# UNDER_FAST.net
KiCad netlist of a schematic drawn in EAGLE
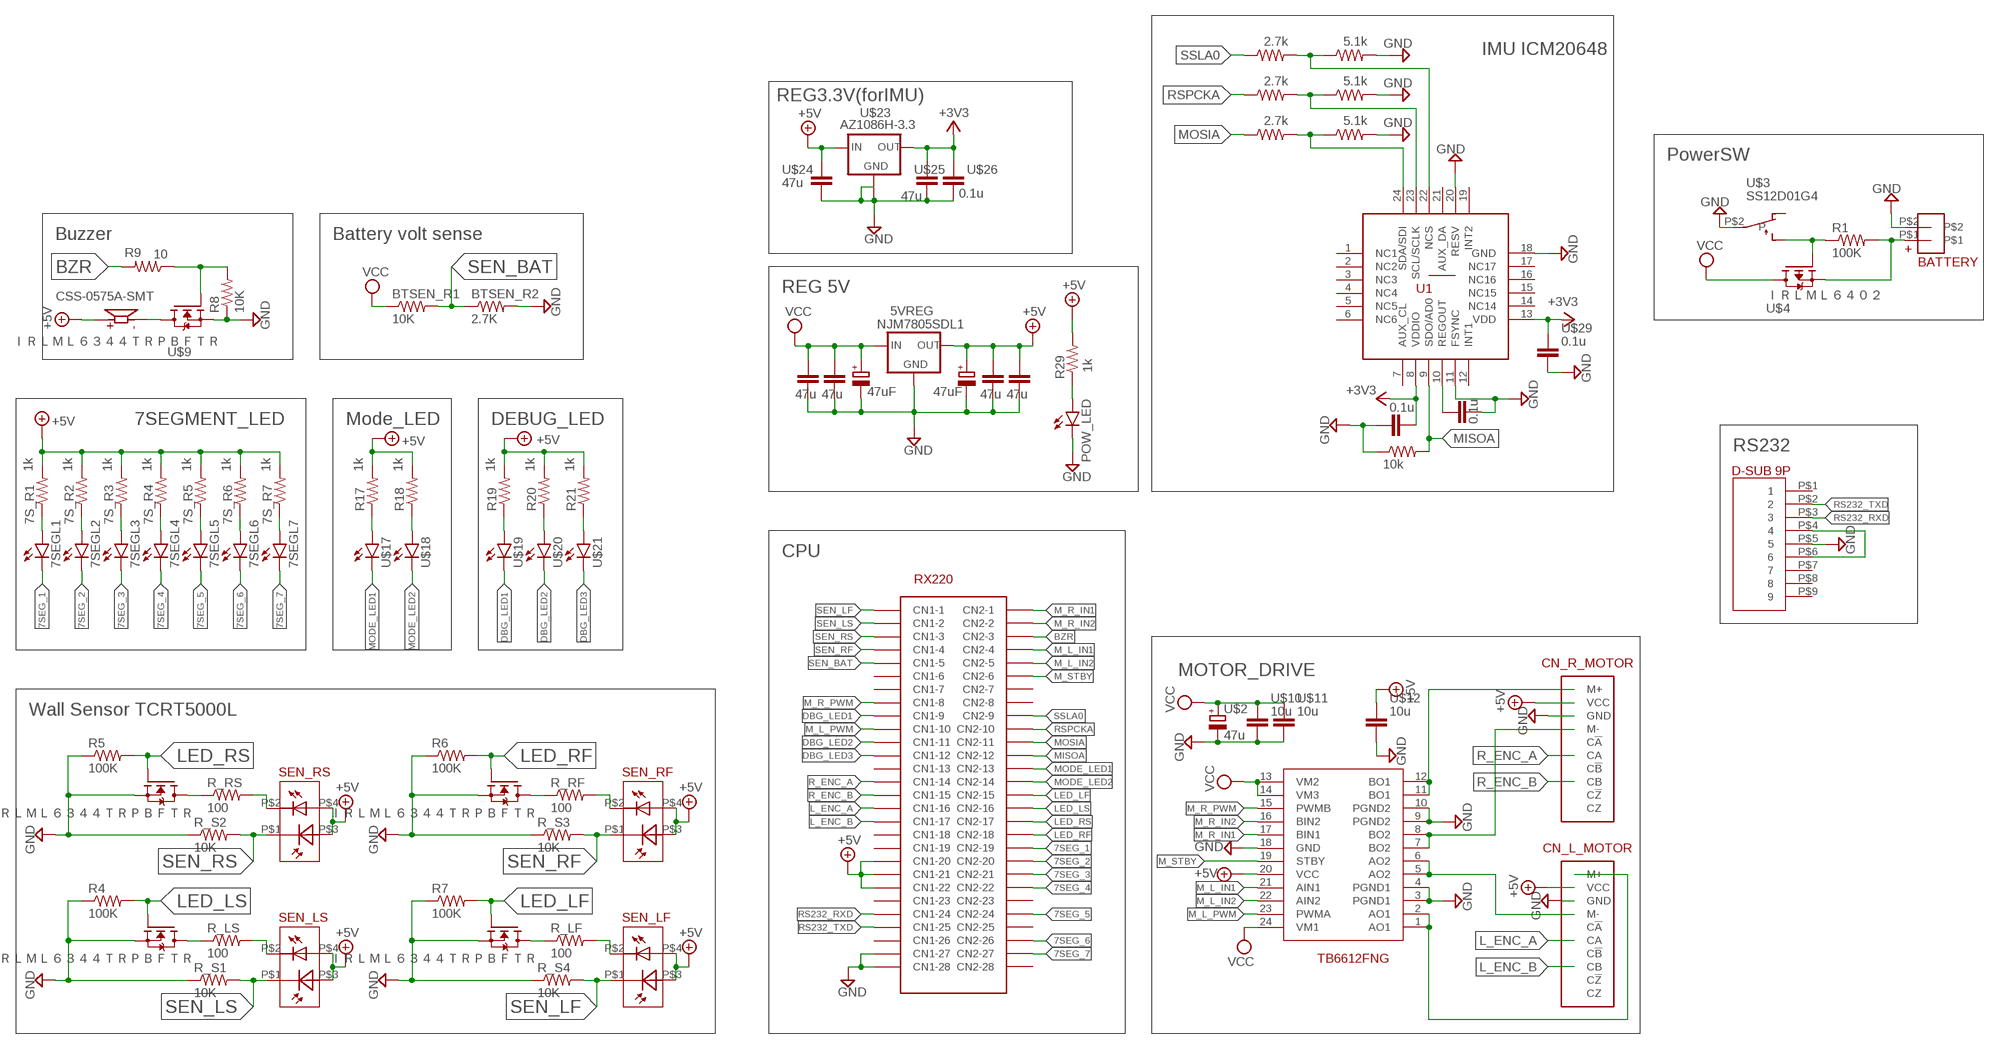
[diagram p0: schematic, sheet 1]

(export (version "E")
  (design (tool "Eeschema 10.0.6"))
  (components
    (comp (ref "5VREG")
      (value "NJM7805SDL1")
      (footprint "eagle-import:TO252")
      (libsource (lib "eagle-import") (part "NJM7805SDL1"))
    )
    (comp (ref "7SEGL1")
      (value "LED1608")
      (footprint "eagle-import:LED1608")
      (libsource (lib "eagle-import") (part "LED1608"))
    )
    (comp (ref "7SEGL2")
      (value "LED1608")
      (footprint "eagle-import:LED1608")
      (libsource (lib "eagle-import") (part "LED1608"))
    )
    (comp (ref "7SEGL3")
      (value "LED1608")
      (footprint "eagle-import:LED1608")
      (libsource (lib "eagle-import") (part "LED1608"))
    )
    (comp (ref "7SEGL4")
      (value "LED1608")
      (footprint "eagle-import:LED1608")
      (libsource (lib "eagle-import") (part "LED1608"))
    )
    (comp (ref "7SEGL5")
      (value "LED1608")
      (footprint "eagle-import:LED1608")
      (libsource (lib "eagle-import") (part "LED1608"))
    )
    (comp (ref "7SEGL6")
      (value "LED1608")
      (footprint "eagle-import:LED1608")
      (libsource (lib "eagle-import") (part "LED1608"))
    )
    (comp (ref "7SEGL7")
      (value "LED1608")
      (footprint "eagle-import:LED1608")
      (libsource (lib "eagle-import") (part "LED1608"))
    )
    (comp (ref "7S_R1")
      (value "1k")
      (footprint "eagle-import:RESC1005X40N")
      (fields
        (field (name "DIGI-KEY_PART_NUMBER") "P1.00KLCT-ND")
        (field (name "MF") "Panasonic")
        (field (name "MP") "ERJ-2RKF1001X")
      )
      (libsource (lib "eagle-import") (part "ERJ-2RKF1001X"))
    )
    (comp (ref "7S_R2")
      (value "1k")
      (footprint "eagle-import:RESC1005X40N")
      (fields
        (field (name "DIGI-KEY_PART_NUMBER") "P1.00KLCT-ND")
        (field (name "MF") "Panasonic")
        (field (name "MP") "ERJ-2RKF1001X")
      )
      (libsource (lib "eagle-import") (part "ERJ-2RKF1001X"))
    )
    (comp (ref "7S_R3")
      (value "1k")
      (footprint "eagle-import:RESC1005X40N")
      (fields
        (field (name "DIGI-KEY_PART_NUMBER") "P1.00KLCT-ND")
        (field (name "MF") "Panasonic")
        (field (name "MP") "ERJ-2RKF1001X")
      )
      (libsource (lib "eagle-import") (part "ERJ-2RKF1001X"))
    )
    (comp (ref "7S_R4")
      (value "1k")
      (footprint "eagle-import:RESC1005X40N")
      (fields
        (field (name "DIGI-KEY_PART_NUMBER") "P1.00KLCT-ND")
        (field (name "MF") "Panasonic")
        (field (name "MP") "ERJ-2RKF1001X")
      )
      (libsource (lib "eagle-import") (part "ERJ-2RKF1001X"))
    )
    (comp (ref "7S_R5")
      (value "1k")
      (footprint "eagle-import:RESC1005X40N")
      (fields
        (field (name "DIGI-KEY_PART_NUMBER") "P1.00KLCT-ND")
        (field (name "MF") "Panasonic")
        (field (name "MP") "ERJ-2RKF1001X")
      )
      (libsource (lib "eagle-import") (part "ERJ-2RKF1001X"))
    )
    (comp (ref "7S_R6")
      (value "1k")
      (footprint "eagle-import:RESC1005X40N")
      (fields
        (field (name "DIGI-KEY_PART_NUMBER") "P1.00KLCT-ND")
        (field (name "MF") "Panasonic")
        (field (name "MP") "ERJ-2RKF1001X")
      )
      (libsource (lib "eagle-import") (part "ERJ-2RKF1001X"))
    )
    (comp (ref "7S_R7")
      (value "1k")
      (footprint "eagle-import:RESC1005X40N")
      (fields
        (field (name "DIGI-KEY_PART_NUMBER") "P1.00KLCT-ND")
        (field (name "MF") "Panasonic")
        (field (name "MP") "ERJ-2RKF1001X")
      )
      (libsource (lib "eagle-import") (part "ERJ-2RKF1001X"))
    )
    (comp (ref "BATTERY")
      (value "DF3A_2P_2DSA_CONNECTOR")
      (footprint "eagle-import:DF3A_2P_2DSA_CONNECTOR")
      (libsource (lib "eagle-import") (part "DF3A_2P_2DSA_CONNECTOR"))
    )
    (comp (ref "BTSEN_R1")
      (value "10K")
      (footprint "eagle-import:RESC1005X40N")
      (fields
        (field (name "DIGI-KEY_PART_NUMBER") "P1.00KLCT-ND")
        (field (name "MF") "Panasonic")
        (field (name "MP") "ERJ-2RKF1001X")
      )
      (libsource (lib "eagle-import") (part "ERJ-2RKF1001X"))
    )
    (comp (ref "BTSEN_R2")
      (value "2.7K")
      (footprint "eagle-import:RESC1005X40N")
      (fields
        (field (name "DIGI-KEY_PART_NUMBER") "P1.00KLCT-ND")
        (field (name "MF") "Panasonic")
        (field (name "MP") "ERJ-2RKF1001X")
      )
      (libsource (lib "eagle-import") (part "ERJ-2RKF1001X"))
    )
    (comp (ref "C1")
      (value "47u")
      (footprint "eagle-import:CAPC3225X270N")
      (libsource (lib "eagle-import") (part "C3225"))
    )
    (comp (ref "C2")
      (value "47u")
      (footprint "eagle-import:CAPC3225X270N")
      (libsource (lib "eagle-import") (part "C3225"))
    )
    (comp (ref "C3")
      (value "47u")
      (footprint "eagle-import:CAPC3225X270N")
      (libsource (lib "eagle-import") (part "C3225"))
    )
    (comp (ref "C4")
      (value "47u")
      (footprint "eagle-import:CAPC3225X270N")
      (libsource (lib "eagle-import") (part "C3225"))
    )
    (comp (ref "CLK_R1")
      (value "2.7k")
      (footprint "eagle-import:RESC1005X40N")
      (fields
        (field (name "DIGI-KEY_PART_NUMBER") "P1.00KLCT-ND")
        (field (name "MF") "Panasonic")
        (field (name "MP") "ERJ-2RKF1001X")
      )
      (libsource (lib "eagle-import") (part "ERJ-2RKF1001X"))
    )
    (comp (ref "CLK_R2")
      (value "5.1k")
      (footprint "eagle-import:RESC1005X40N")
      (fields
        (field (name "DIGI-KEY_PART_NUMBER") "P1.00KLCT-ND")
        (field (name "MF") "Panasonic")
        (field (name "MP") "ERJ-2RKF1001X")
      )
      (libsource (lib "eagle-import") (part "ERJ-2RKF1001X"))
    )
    (comp (ref "CN_L_MOTOR")
      (value "CN_MOTOR")
      (footprint "eagle-import:CN_MOTOR")
      (libsource (lib "eagle-import") (part "CN_MOTOR"))
    )
    (comp (ref "CN_R_MOTOR")
      (value "CN_MOTOR")
      (footprint "eagle-import:CN_MOTOR")
      (libsource (lib "eagle-import") (part "CN_MOTOR"))
    )
    (comp (ref "EC1")
      (value "47uF")
      (footprint "eagle-import:CAPAE660X800N")
      (libsource (lib "eagle-import") (part "EEE-HC1E470XP"))
    )
    (comp (ref "EC2")
      (value "47uF")
      (footprint "eagle-import:CAPAE660X800N")
      (libsource (lib "eagle-import") (part "EEE-HC1E470XP"))
    )
    (comp (ref "LS1")
      (value "CSS-0575A-SMT")
      (footprint "eagle-import:CUI_CSS-0575A-SMT")
      (fields
        (field (name "DIGI-KEY_PART_NUMBER") "102-2201-1-ND")
        (field (name "MF") "CUI Devices")
        (field (name "MP") "CSS-0575A-SMT-TR")
      )
      (libsource (lib "eagle-import") (part "CSS-0575A-SMT"))
    )
    (comp (ref "MISO_R")
      (value "10k")
      (footprint "eagle-import:RESC1005X40N")
      (fields
        (field (name "DIGI-KEY_PART_NUMBER") "P1.00KLCT-ND")
        (field (name "MF") "Panasonic")
        (field (name "MP") "ERJ-2RKF1001X")
      )
      (libsource (lib "eagle-import") (part "ERJ-2RKF1001X"))
    )
    (comp (ref "MOSI_R1")
      (value "2.7k")
      (footprint "eagle-import:RESC1005X40N")
      (fields
        (field (name "DIGI-KEY_PART_NUMBER") "P1.00KLCT-ND")
        (field (name "MF") "Panasonic")
        (field (name "MP") "ERJ-2RKF1001X")
      )
      (libsource (lib "eagle-import") (part "ERJ-2RKF1001X"))
    )
    (comp (ref "MOSI_R2")
      (value "5.1k")
      (footprint "eagle-import:RESC1005X40N")
      (fields
        (field (name "DIGI-KEY_PART_NUMBER") "P1.00KLCT-ND")
        (field (name "MF") "Panasonic")
        (field (name "MP") "ERJ-2RKF1001X")
      )
      (libsource (lib "eagle-import") (part "ERJ-2RKF1001X"))
    )
    (comp (ref "NCS_R1")
      (value "2.7k")
      (footprint "eagle-import:RESC1005X40N")
      (fields
        (field (name "DIGI-KEY_PART_NUMBER") "P1.00KLCT-ND")
        (field (name "MF") "Panasonic")
        (field (name "MP") "ERJ-2RKF1001X")
      )
      (libsource (lib "eagle-import") (part "ERJ-2RKF1001X"))
    )
    (comp (ref "NCS_R2")
      (value "5.1k")
      (footprint "eagle-import:RESC1005X40N")
      (fields
        (field (name "DIGI-KEY_PART_NUMBER") "P1.00KLCT-ND")
        (field (name "MF") "Panasonic")
        (field (name "MP") "ERJ-2RKF1001X")
      )
      (libsource (lib "eagle-import") (part "ERJ-2RKF1001X"))
    )
    (comp (ref "POW_LED")
      (value "LED1608")
      (footprint "eagle-import:LED1608")
      (libsource (lib "eagle-import") (part "LED1608"))
    )
    (comp (ref "R1")
      (value "100K")
      (footprint "eagle-import:RESC1005X40N")
      (fields
        (field (name "DIGI-KEY_PART_NUMBER") "P1.00KLCT-ND")
        (field (name "MF") "Panasonic")
        (field (name "MP") "ERJ-2RKF1001X")
      )
      (libsource (lib "eagle-import") (part "ERJ-2RKF1001X"))
    )
    (comp (ref "R4")
      (value "100K")
      (footprint "eagle-import:RESC1005X40N")
      (fields
        (field (name "DIGI-KEY_PART_NUMBER") "P1.00KLCT-ND")
        (field (name "MF") "Panasonic")
        (field (name "MP") "ERJ-2RKF1001X")
      )
      (libsource (lib "eagle-import") (part "ERJ-2RKF1001X"))
    )
    (comp (ref "R5")
      (value "100K")
      (footprint "eagle-import:RESC1005X40N")
      (fields
        (field (name "DIGI-KEY_PART_NUMBER") "P1.00KLCT-ND")
        (field (name "MF") "Panasonic")
        (field (name "MP") "ERJ-2RKF1001X")
      )
      (libsource (lib "eagle-import") (part "ERJ-2RKF1001X"))
    )
    (comp (ref "R6")
      (value "100K")
      (footprint "eagle-import:RESC1005X40N")
      (fields
        (field (name "DIGI-KEY_PART_NUMBER") "P1.00KLCT-ND")
        (field (name "MF") "Panasonic")
        (field (name "MP") "ERJ-2RKF1001X")
      )
      (libsource (lib "eagle-import") (part "ERJ-2RKF1001X"))
    )
    (comp (ref "R7")
      (value "100K")
      (footprint "eagle-import:RESC1005X40N")
      (fields
        (field (name "DIGI-KEY_PART_NUMBER") "P1.00KLCT-ND")
        (field (name "MF") "Panasonic")
        (field (name "MP") "ERJ-2RKF1001X")
      )
      (libsource (lib "eagle-import") (part "ERJ-2RKF1001X"))
    )
    (comp (ref "R8")
      (value "10K")
      (footprint "eagle-import:RESC1005X40N")
      (fields
        (field (name "DIGI-KEY_PART_NUMBER") "P1.00KLCT-ND")
        (field (name "MF") "Panasonic")
        (field (name "MP") "ERJ-2RKF1001X")
      )
      (libsource (lib "eagle-import") (part "ERJ-2RKF1001X"))
    )
    (comp (ref "R9")
      (value "10")
      (footprint "eagle-import:RESC1005X40N")
      (fields
        (field (name "DIGI-KEY_PART_NUMBER") "P1.00KLCT-ND")
        (field (name "MF") "Panasonic")
        (field (name "MP") "ERJ-2RKF1001X")
      )
      (libsource (lib "eagle-import") (part "ERJ-2RKF1001X"))
    )
    (comp (ref "R17")
      (value "1k")
      (footprint "eagle-import:RESC1005X40N")
      (fields
        (field (name "DIGI-KEY_PART_NUMBER") "P1.00KLCT-ND")
        (field (name "MF") "Panasonic")
        (field (name "MP") "ERJ-2RKF1001X")
      )
      (libsource (lib "eagle-import") (part "ERJ-2RKF1001X"))
    )
    (comp (ref "R18")
      (value "1k")
      (footprint "eagle-import:RESC1005X40N")
      (fields
        (field (name "DIGI-KEY_PART_NUMBER") "P1.00KLCT-ND")
        (field (name "MF") "Panasonic")
        (field (name "MP") "ERJ-2RKF1001X")
      )
      (libsource (lib "eagle-import") (part "ERJ-2RKF1001X"))
    )
    (comp (ref "R19")
      (value "1k")
      (footprint "eagle-import:RESC1005X40N")
      (fields
        (field (name "DIGI-KEY_PART_NUMBER") "P1.00KLCT-ND")
        (field (name "MF") "Panasonic")
        (field (name "MP") "ERJ-2RKF1001X")
      )
      (libsource (lib "eagle-import") (part "ERJ-2RKF1001X"))
    )
    (comp (ref "R20")
      (value "1k")
      (footprint "eagle-import:RESC1005X40N")
      (fields
        (field (name "DIGI-KEY_PART_NUMBER") "P1.00KLCT-ND")
        (field (name "MF") "Panasonic")
        (field (name "MP") "ERJ-2RKF1001X")
      )
      (libsource (lib "eagle-import") (part "ERJ-2RKF1001X"))
    )
    (comp (ref "R21")
      (value "1k")
      (footprint "eagle-import:RESC1005X40N")
      (fields
        (field (name "DIGI-KEY_PART_NUMBER") "P1.00KLCT-ND")
        (field (name "MF") "Panasonic")
        (field (name "MP") "ERJ-2RKF1001X")
      )
      (libsource (lib "eagle-import") (part "ERJ-2RKF1001X"))
    )
    (comp (ref "R29")
      (value "1k")
      (footprint "eagle-import:RESC1005X40N")
      (fields
        (field (name "DIGI-KEY_PART_NUMBER") "P1.00KLCT-ND")
        (field (name "MF") "Panasonic")
        (field (name "MP") "ERJ-2RKF1001X")
      )
      (libsource (lib "eagle-import") (part "ERJ-2RKF1001X"))
    )
    (comp (ref "R_LF")
      (value "100")
      (footprint "eagle-import:RESC1005X40N")
      (fields
        (field (name "DIGI-KEY_PART_NUMBER") "P1.00KLCT-ND")
        (field (name "MF") "Panasonic")
        (field (name "MP") "ERJ-2RKF1001X")
      )
      (libsource (lib "eagle-import") (part "ERJ-2RKF1001X"))
    )
    (comp (ref "R_LS")
      (value "100")
      (footprint "eagle-import:RESC1005X40N")
      (fields
        (field (name "DIGI-KEY_PART_NUMBER") "P1.00KLCT-ND")
        (field (name "MF") "Panasonic")
        (field (name "MP") "ERJ-2RKF1001X")
      )
      (libsource (lib "eagle-import") (part "ERJ-2RKF1001X"))
    )
    (comp (ref "R_RF")
      (value "100")
      (footprint "eagle-import:RESC1005X40N")
      (fields
        (field (name "DIGI-KEY_PART_NUMBER") "P1.00KLCT-ND")
        (field (name "MF") "Panasonic")
        (field (name "MP") "ERJ-2RKF1001X")
      )
      (libsource (lib "eagle-import") (part "ERJ-2RKF1001X"))
    )
    (comp (ref "R_RS")
      (value "100")
      (footprint "eagle-import:RESC1005X40N")
      (fields
        (field (name "DIGI-KEY_PART_NUMBER") "P1.00KLCT-ND")
        (field (name "MF") "Panasonic")
        (field (name "MP") "ERJ-2RKF1001X")
      )
      (libsource (lib "eagle-import") (part "ERJ-2RKF1001X"))
    )
    (comp (ref "R_S1")
      (value "10K")
      (footprint "eagle-import:RESC1005X40N")
      (fields
        (field (name "DIGI-KEY_PART_NUMBER") "P1.00KLCT-ND")
        (field (name "MF") "Panasonic")
        (field (name "MP") "ERJ-2RKF1001X")
      )
      (libsource (lib "eagle-import") (part "ERJ-2RKF1001X"))
    )
    (comp (ref "R_S2")
      (value "10K")
      (footprint "eagle-import:RESC1005X40N")
      (fields
        (field (name "DIGI-KEY_PART_NUMBER") "P1.00KLCT-ND")
        (field (name "MF") "Panasonic")
        (field (name "MP") "ERJ-2RKF1001X")
      )
      (libsource (lib "eagle-import") (part "ERJ-2RKF1001X"))
    )
    (comp (ref "R_S3")
      (value "10K")
      (footprint "eagle-import:RESC1005X40N")
      (fields
        (field (name "DIGI-KEY_PART_NUMBER") "P1.00KLCT-ND")
        (field (name "MF") "Panasonic")
        (field (name "MP") "ERJ-2RKF1001X")
      )
      (libsource (lib "eagle-import") (part "ERJ-2RKF1001X"))
    )
    (comp (ref "R_S4")
      (value "10K")
      (footprint "eagle-import:RESC1005X40N")
      (fields
        (field (name "DIGI-KEY_PART_NUMBER") "P1.00KLCT-ND")
        (field (name "MF") "Panasonic")
        (field (name "MP") "ERJ-2RKF1001X")
      )
      (libsource (lib "eagle-import") (part "ERJ-2RKF1001X"))
    )
    (comp (ref "SEN_LF")
      (value "TCRT5000L")
      (footprint "eagle-import:TCRT5000L_PHOTO")
      (libsource (lib "eagle-import") (part "TCRT5000L"))
    )
    (comp (ref "SEN_LS")
      (value "TCRT5000L")
      (footprint "eagle-import:TCRT5000L_PHOTO")
      (libsource (lib "eagle-import") (part "TCRT5000L"))
    )
    (comp (ref "SEN_RF")
      (value "TCRT5000L")
      (footprint "eagle-import:TCRT5000L_PHOTO")
      (libsource (lib "eagle-import") (part "TCRT5000L"))
    )
    (comp (ref "SEN_RS")
      (value "TCRT5000L")
      (footprint "eagle-import:TCRT5000L_PHOTO")
      (libsource (lib "eagle-import") (part "TCRT5000L"))
    )
    (comp (ref "TB6612FNG")
      (value "TB6612FNG")
      (footprint "eagle-import:SOP65P760X160-24N")
      (libsource (lib "eagle-import") (part "TB6612FNG"))
    )
    (comp (ref "U$1")
      (value "RX220_BOARD")
      (footprint "eagle-import:RX220_BOARD")
      (libsource (lib "eagle-import") (part "RX220_BOARD"))
    )
    (comp (ref "U$2")
      (value "47u")
      (footprint "eagle-import:CAPAE660X800N")
      (libsource (lib "eagle-import") (part "EEE-HC1E470XP"))
    )
    (comp (ref "U$3")
      (value "SS12D01G4")
      (footprint "eagle-import:SS12D01G4")
      (libsource (lib "eagle-import") (part "SS12D01G4"))
    )
    (comp (ref "U$4")
      (value "ＩＲＬＭＬ６４０２")
      (footprint "eagle-import:SOT23")
      (libsource (lib "eagle-import") (part "ＩＲＬＭＬ６４０２"))
    )
    (comp (ref "U$5")
      (value "ＩＲＬＭＬ６３４４ＴＲＰＢＦＴＲ")
      (footprint "eagle-import:SOT23")
      (libsource (lib "eagle-import") (part "ＩＲＬＭＬ６３４４ＴＲＰＢＦＴＲ"))
    )
    (comp (ref "U$6")
      (value "ＩＲＬＭＬ６３４４ＴＲＰＢＦＴＲ")
      (footprint "eagle-import:SOT23")
      (libsource (lib "eagle-import") (part "ＩＲＬＭＬ６３４４ＴＲＰＢＦＴＲ"))
    )
    (comp (ref "U$7")
      (value "ＩＲＬＭＬ６３４４ＴＲＰＢＦＴＲ")
      (footprint "eagle-import:SOT23")
      (libsource (lib "eagle-import") (part "ＩＲＬＭＬ６３４４ＴＲＰＢＦＴＲ"))
    )
    (comp (ref "U$8")
      (value "ＩＲＬＭＬ６３４４ＴＲＰＢＦＴＲ")
      (footprint "eagle-import:SOT23")
      (libsource (lib "eagle-import") (part "ＩＲＬＭＬ６３４４ＴＲＰＢＦＴＲ"))
    )
    (comp (ref "U$9")
      (value "ＩＲＬＭＬ６３４４ＴＲＰＢＦＴＲ")
      (footprint "eagle-import:SOT23")
      (libsource (lib "eagle-import") (part "ＩＲＬＭＬ６３４４ＴＲＰＢＦＴＲ"))
    )
    (comp (ref "U$10")
      (value "10u")
      (footprint "eagle-import:CAPC3216X180N")
      (libsource (lib "eagle-import") (part "CL31A106KBHNNNE"))
    )
    (comp (ref "U$11")
      (value "10u")
      (footprint "eagle-import:CAPC3216X180N")
      (libsource (lib "eagle-import") (part "CL31A106KBHNNNE"))
    )
    (comp (ref "U$12")
      (value "10u")
      (footprint "eagle-import:CAPC3216X180N")
      (libsource (lib "eagle-import") (part "CL31A106KBHNNNE"))
    )
    (comp (ref "U$13")
      (value "D-SUB")
      (footprint "eagle-import:D-SUB")
      (libsource (lib "eagle-import") (part "D-SUB"))
    )
    (comp (ref "U$17")
      (value "LED1608")
      (footprint "eagle-import:LED1608")
      (libsource (lib "eagle-import") (part "LED1608"))
    )
    (comp (ref "U$18")
      (value "LED1608")
      (footprint "eagle-import:LED1608")
      (libsource (lib "eagle-import") (part "LED1608"))
    )
    (comp (ref "U$19")
      (value "LED1608")
      (footprint "eagle-import:LED1608")
      (libsource (lib "eagle-import") (part "LED1608"))
    )
    (comp (ref "U$20")
      (value "LED1608")
      (footprint "eagle-import:LED1608")
      (libsource (lib "eagle-import") (part "LED1608"))
    )
    (comp (ref "U$21")
      (value "LED1608")
      (footprint "eagle-import:LED1608")
      (libsource (lib "eagle-import") (part "LED1608"))
    )
    (comp (ref "U$23")
      (value "AZ1086H-3.3")
      (footprint "eagle-import:SOT223")
      (libsource (lib "eagle-import") (part "AZ1086H-3.3"))
    )
    (comp (ref "U$24")
      (value "47u")
      (footprint "eagle-import:CAPC3225X270N")
      (libsource (lib "eagle-import") (part "C3225"))
    )
    (comp (ref "U$25")
      (value "47u")
      (footprint "eagle-import:CAPC3225X270N")
      (libsource (lib "eagle-import") (part "C3225"))
    )
    (comp (ref "U$26")
      (value "0.1u")
      (footprint "eagle-import:CAPC1005X55N")
      (libsource (lib "eagle-import") (part "C1005"))
    )
    (comp (ref "U$27")
      (value "0.1u")
      (footprint "eagle-import:CAPC1005X55N")
      (libsource (lib "eagle-import") (part "C1005"))
    )
    (comp (ref "U$28")
      (value "0.1u")
      (footprint "eagle-import:CAPC1005X55N")
      (libsource (lib "eagle-import") (part "C1005"))
    )
    (comp (ref "U$29")
      (value "0.1u")
      (footprint "eagle-import:CAPC1005X55N")
      (libsource (lib "eagle-import") (part "C1005"))
    )
    (comp (ref "U1")
      (value "ICM-20648")
      (footprint "eagle-import:QFN40P300X300X95-24N")
      (fields (field (name "DIGI-KEY_PART_NUMBER") "1428-1061-1-ND") (field (name "MF") "TDK InvenSense"))
      (libsource (lib "eagle-import") (part "ICM-20648"))
    )
  )
  (nets
    (net (code "1") (name "+3V3") (class "Default")
      (node (ref "U$23") (pin "2") (pinfunction "OUT_2") (pintype "passive"))
      (node (ref "U$25") (pin "1") (pinfunction "1_1") (pintype "passive"))
      (node (ref "U$26") (pin "1") (pinfunction "1_1") (pintype "passive"))
      (node (ref "U$28") (pin "1") (pinfunction "1_1") (pintype "passive"))
      (node (ref "U$29") (pin "1") (pinfunction "1_1") (pintype "passive"))
      (node (ref "U1") (pin "13") (pinfunction "VDD_13") (pintype "bidirectional"))
      (node (ref "U1") (pin "8") (pinfunction "VDDIO_8") (pintype "bidirectional"))
    )
    (net (code "2") (name "+5V") (class "Default")
      (node (ref "5VREG") (pin "2") (pinfunction "OUT_2") (pintype "passive"))
      (node (ref "7S_R1") (pin "2") (pinfunction "2_2") (pintype "passive"))
      (node (ref "7S_R2") (pin "2") (pinfunction "2_2") (pintype "passive"))
      (node (ref "7S_R3") (pin "2") (pinfunction "2_2") (pintype "passive"))
      (node (ref "7S_R4") (pin "2") (pinfunction "2_2") (pintype "passive"))
      (node (ref "7S_R5") (pin "2") (pinfunction "2_2") (pintype "passive"))
      (node (ref "7S_R6") (pin "2") (pinfunction "2_2") (pintype "passive"))
      (node (ref "7S_R7") (pin "2") (pinfunction "2_2") (pintype "passive"))
      (node (ref "C3") (pin "1") (pinfunction "1_1") (pintype "passive"))
      (node (ref "C4") (pin "1") (pinfunction "1_1") (pintype "passive"))
      (node (ref "CN_L_MOTOR") (pin "P$2") (pinfunction "VCC_P$2") (pintype "bidirectional"))
      (node (ref "CN_R_MOTOR") (pin "P$2") (pinfunction "VCC_P$2") (pintype "bidirectional"))
      (node (ref "EC2") (pin "1") (pinfunction "+_1") (pintype "passive"))
      (node (ref "LS1") (pin "1") (pinfunction "P_1") (pintype "passive"))
      (node (ref "R17") (pin "2") (pinfunction "2_2") (pintype "passive"))
      (node (ref "R18") (pin "2") (pinfunction "2_2") (pintype "passive"))
      (node (ref "R19") (pin "2") (pinfunction "2_2") (pintype "passive"))
      (node (ref "R20") (pin "2") (pinfunction "2_2") (pintype "passive"))
      (node (ref "R21") (pin "2") (pinfunction "2_2") (pintype "passive"))
      (node (ref "R29") (pin "2") (pinfunction "2_2") (pintype "passive"))
      (node (ref "SEN_LF") (pin "P$3") (pinfunction "DIODE+_P$3") (pintype "bidirectional"))
      (node (ref "SEN_LF") (pin "P$4") (pinfunction "LED+_P$4") (pintype "bidirectional"))
      (node (ref "SEN_LS") (pin "P$3") (pinfunction "DIODE+_P$3") (pintype "bidirectional"))
      (node (ref "SEN_LS") (pin "P$4") (pinfunction "LED+_P$4") (pintype "bidirectional"))
      (node (ref "SEN_RF") (pin "P$3") (pinfunction "DIODE+_P$3") (pintype "bidirectional"))
      (node (ref "SEN_RF") (pin "P$4") (pinfunction "LED+_P$4") (pintype "bidirectional"))
      (node (ref "SEN_RS") (pin "P$3") (pinfunction "DIODE+_P$3") (pintype "bidirectional"))
      (node (ref "SEN_RS") (pin "P$4") (pinfunction "LED+_P$4") (pintype "bidirectional"))
      (node (ref "TB6612FNG") (pin "20") (pinfunction "VCC_20") (pintype "bidirectional"))
      (node (ref "U$1") (pin "P$20") (pinfunction "CN1-20_P$20") (pintype "bidirectional"))
      (node (ref "U$1") (pin "P$21") (pinfunction "CN1-21_P$21") (pintype "bidirectional"))
      (node (ref "U$1") (pin "P$22") (pinfunction "CN1-22_P$22") (pintype "bidirectional"))
      (node (ref "U$12") (pin "1") (pinfunction "1_1") (pintype "passive"))
      (node (ref "U$23") (pin "3") (pinfunction "IN_3") (pintype "input"))
      (node (ref "U$24") (pin "1") (pinfunction "1_1") (pintype "passive"))
    )
    (net (code "3") (name "7SEG_1") (class "Default")
      (node (ref "7SEGL1") (pin "P$2") (pinfunction "C_P$2") (pintype "passive"))
      (node (ref "U$1") (pin "P$47") (pinfunction "CN2-19_P$47") (pintype "bidirectional"))
    )
    (net (code "4") (name "7SEG_2") (class "Default")
      (node (ref "7SEGL2") (pin "P$2") (pinfunction "C_P$2") (pintype "passive"))
      (node (ref "U$1") (pin "P$48") (pinfunction "CN2-20_P$48") (pintype "bidirectional"))
    )
    (net (code "5") (name "7SEG_3") (class "Default")
      (node (ref "7SEGL3") (pin "P$2") (pinfunction "C_P$2") (pintype "passive"))
      (node (ref "U$1") (pin "P$49") (pinfunction "CN2-21_P$49") (pintype "bidirectional"))
    )
    (net (code "6") (name "7SEG_4") (class "Default")
      (node (ref "7SEGL4") (pin "P$2") (pinfunction "C_P$2") (pintype "passive"))
      (node (ref "U$1") (pin "P$50") (pinfunction "CN2-22_P$50") (pintype "bidirectional"))
    )
    (net (code "7") (name "7SEG_5") (class "Default")
      (node (ref "7SEGL5") (pin "P$2") (pinfunction "C_P$2") (pintype "passive"))
      (node (ref "U$1") (pin "P$52") (pinfunction "CN2-24_P$52") (pintype "bidirectional"))
    )
    (net (code "8") (name "7SEG_6") (class "Default")
      (node (ref "7SEGL6") (pin "P$2") (pinfunction "C_P$2") (pintype "passive"))
      (node (ref "U$1") (pin "P$54") (pinfunction "CN2-26_P$54") (pintype "bidirectional"))
    )
    (net (code "9") (name "7SEG_7") (class "Default")
      (node (ref "7SEGL7") (pin "P$2") (pinfunction "C_P$2") (pintype "passive"))
      (node (ref "U$1") (pin "P$55") (pinfunction "CN2-27_P$55") (pintype "bidirectional"))
    )
    (net (code "10") (name "BZR") (class "Default")
      (node (ref "R9") (pin "2") (pinfunction "2_2") (pintype "passive"))
      (node (ref "U$1") (pin "P$31") (pinfunction "CN2-3_P$31") (pintype "bidirectional"))
    )
    (net (code "11") (name "DBG_LED1") (class "Default")
      (node (ref "U$1") (pin "P$9") (pinfunction "CN1-9_P$9") (pintype "bidirectional"))
      (node (ref "U$19") (pin "P$2") (pinfunction "C_P$2") (pintype "passive"))
    )
    (net (code "12") (name "DBG_LED2") (class "Default")
      (node (ref "U$1") (pin "P$11") (pinfunction "CN1-11_P$11") (pintype "bidirectional"))
      (node (ref "U$20") (pin "P$2") (pinfunction "C_P$2") (pintype "passive"))
    )
    (net (code "13") (name "DBG_LED3") (class "Default")
      (node (ref "U$1") (pin "P$12") (pinfunction "CN1-12_P$12") (pintype "bidirectional"))
      (node (ref "U$21") (pin "P$2") (pinfunction "C_P$2") (pintype "passive"))
    )
    (net (code "14") (name "GND") (class "Default")
      (node (ref "5VREG") (pin "3") (pinfunction "GND_3") (pintype "input"))
      (node (ref "BATTERY") (pin "P$2") (pinfunction "P$2_P$2") (pintype "bidirectional"))
      (node (ref "BTSEN_R2") (pin "2") (pinfunction "2_2") (pintype "passive"))
      (node (ref "C1") (pin "2") (pinfunction "2_2") (pintype "passive"))
      (node (ref "C2") (pin "2") (pinfunction "2_2") (pintype "passive"))
      (node (ref "C3") (pin "2") (pinfunction "2_2") (pintype "passive"))
      (node (ref "C4") (pin "2") (pinfunction "2_2") (pintype "passive"))
      (node (ref "CLK_R2") (pin "2") (pinfunction "2_2") (pintype "passive"))
      (node (ref "CN_L_MOTOR") (pin "P$3") (pinfunction "GND_P$3") (pintype "bidirectional"))
      (node (ref "CN_R_MOTOR") (pin "P$3") (pinfunction "GND_P$3") (pintype "bidirectional"))
      (node (ref "EC1") (pin "2") (pinfunction "-_2") (pintype "passive"))
      (node (ref "EC2") (pin "2") (pinfunction "-_2") (pintype "passive"))
      (node (ref "MISO_R") (pin "1") (pinfunction "1_1") (pintype "passive"))
      (node (ref "MOSI_R2") (pin "2") (pinfunction "2_2") (pintype "passive"))
      (node (ref "NCS_R2") (pin "2") (pinfunction "2_2") (pintype "passive"))
      (node (ref "POW_LED") (pin "P$2") (pinfunction "C_P$2") (pintype "passive"))
      (node (ref "R4") (pin "1") (pinfunction "1_1") (pintype "passive"))
      (node (ref "R5") (pin "1") (pinfunction "1_1") (pintype "passive"))
      (node (ref "R6") (pin "1") (pinfunction "1_1") (pintype "passive"))
      (node (ref "R7") (pin "1") (pinfunction "1_1") (pintype "passive"))
      (node (ref "R8") (pin "1") (pinfunction "1_1") (pintype "passive"))
      (node (ref "R_S1") (pin "1") (pinfunction "1_1") (pintype "passive"))
      (node (ref "R_S2") (pin "1") (pinfunction "1_1") (pintype "passive"))
      (node (ref "R_S3") (pin "1") (pinfunction "1_1") (pintype "passive"))
      (node (ref "R_S4") (pin "1") (pinfunction "1_1") (pintype "passive"))
      (node (ref "TB6612FNG") (pin "10") (pinfunction "PGND2_10") (pintype "bidirectional"))
      (node (ref "TB6612FNG") (pin "18") (pinfunction "GND_18") (pintype "bidirectional"))
      (node (ref "TB6612FNG") (pin "3") (pinfunction "PGND1_3") (pintype "bidirectional"))
      (node (ref "TB6612FNG") (pin "4") (pinfunction "PGND1_4") (pintype "bidirectional"))
      (node (ref "TB6612FNG") (pin "9") (pinfunction "PGND2_9") (pintype "bidirectional"))
      (node (ref "U$1") (pin "P$27") (pinfunction "CN1-27_P$27") (pintype "bidirectional"))
      (node (ref "U$1") (pin "P$28") (pinfunction "CN1-28_P$28") (pintype "bidirectional"))
      (node (ref "U$10") (pin "2") (pinfunction "2_2") (pintype "passive"))
      (node (ref "U$11") (pin "2") (pinfunction "2_2") (pintype "passive"))
      (node (ref "U$12") (pin "2") (pinfunction "2_2") (pintype "passive"))
      (node (ref "U$13") (pin "P$5") (pinfunction "5_P$5") (pintype "bidirectional"))
      (node (ref "U$2") (pin "2") (pinfunction "-_2") (pintype "passive"))
      (node (ref "U$23") (pin "1") (pinfunction "GND_1") (pintype "input"))
      (node (ref "U$23") (pin "4") (pinfunction "GND1_4") (pintype "input"))
      (node (ref "U$24") (pin "2") (pinfunction "2_2") (pintype "passive"))
      (node (ref "U$25") (pin "2") (pinfunction "2_2") (pintype "passive"))
      (node (ref "U$26") (pin "2") (pinfunction "2_2") (pintype "passive"))
      (node (ref "U$27") (pin "2") (pinfunction "2_2") (pintype "passive"))
      (node (ref "U$28") (pin "2") (pinfunction "2_2") (pintype "passive"))
      (node (ref "U$29") (pin "2") (pinfunction "2_2") (pintype "passive"))
      (node (ref "U$3") (pin "P$2") (pinfunction "P_P$2") (pintype "passive"))
      (node (ref "U$5") (pin "2") (pinfunction "S_2") (pintype "passive"))
      (node (ref "U$6") (pin "2") (pinfunction "S_2") (pintype "passive"))
      (node (ref "U$7") (pin "2") (pinfunction "S_2") (pintype "passive"))
      (node (ref "U$8") (pin "2") (pinfunction "S_2") (pintype "passive"))
      (node (ref "U$9") (pin "2") (pinfunction "S_2") (pintype "passive"))
      (node (ref "U1") (pin "11") (pinfunction "FSYNC_11") (pintype "bidirectional"))
      (node (ref "U1") (pin "18") (pinfunction "GND_18") (pintype "bidirectional"))
      (node (ref "U1") (pin "20") (pinfunction "RESV_20") (pintype "bidirectional"))
    )
    (net (code "15") (name "LED_LF") (class "Default")
      (node (ref "R7") (pin "2") (pinfunction "2_2") (pintype "passive"))
      (node (ref "U$1") (pin "P$43") (pinfunction "CN2-15_P$43") (pintype "bidirectional"))
      (node (ref "U$8") (pin "1") (pinfunction "G_1") (pintype "passive"))
    )
    (net (code "16") (name "LED_LS") (class "Default")
      (node (ref "R4") (pin "2") (pinfunction "2_2") (pintype "passive"))
      (node (ref "U$1") (pin "P$44") (pinfunction "CN2-16_P$44") (pintype "bidirectional"))
      (node (ref "U$6") (pin "1") (pinfunction "G_1") (pintype "passive"))
    )
    (net (code "17") (name "LED_RF") (class "Default")
      (node (ref "R6") (pin "2") (pinfunction "2_2") (pintype "passive"))
      (node (ref "U$1") (pin "P$46") (pinfunction "CN2-18_P$46") (pintype "bidirectional"))
      (node (ref "U$7") (pin "1") (pinfunction "G_1") (pintype "passive"))
    )
    (net (code "18") (name "LED_RS") (class "Default")
      (node (ref "R5") (pin "2") (pinfunction "2_2") (pintype "passive"))
      (node (ref "U$1") (pin "P$45") (pinfunction "CN2-17_P$45") (pintype "bidirectional"))
      (node (ref "U$5") (pin "1") (pinfunction "G_1") (pintype "passive"))
    )
    (net (code "19") (name "L_ENC_A") (class "Default")
      (node (ref "CN_L_MOTOR") (pin "P$6") (pinfunction "CA_P$6") (pintype "bidirectional"))
      (node (ref "U$1") (pin "P$16") (pinfunction "CN1-16_P$16") (pintype "bidirectional"))
    )
    (net (code "20") (name "L_ENC_B") (class "Default")
      (node (ref "CN_L_MOTOR") (pin "P$8") (pinfunction "CB_P$8") (pintype "bidirectional"))
      (node (ref "U$1") (pin "P$17") (pinfunction "CN1-17_P$17") (pintype "bidirectional"))
    )
    (net (code "21") (name "MISOA") (class "Default")
      (node (ref "MISO_R") (pin "2") (pinfunction "2_2") (pintype "passive"))
      (node (ref "U$1") (pin "P$40") (pinfunction "CN2-12_P$40") (pintype "bidirectional"))
      (node (ref "U1") (pin "9") (pinfunction "SDO/AD0_9") (pintype "bidirectional"))
    )
    (net (code "22") (name "MODE_LED1") (class "Default")
      (node (ref "U$1") (pin "P$41") (pinfunction "CN2-13_P$41") (pintype "bidirectional"))
      (node (ref "U$17") (pin "P$2") (pinfunction "C_P$2") (pintype "passive"))
    )
    (net (code "23") (name "MODE_LED2") (class "Default")
      (node (ref "U$1") (pin "P$42") (pinfunction "CN2-14_P$42") (pintype "bidirectional"))
      (node (ref "U$18") (pin "P$2") (pinfunction "C_P$2") (pintype "passive"))
    )
    (net (code "24") (name "MOSIA") (class "Default")
      (node (ref "MOSI_R1") (pin "1") (pinfunction "1_1") (pintype "passive"))
      (node (ref "U$1") (pin "P$39") (pinfunction "CN2-11_P$39") (pintype "bidirectional"))
    )
    (net (code "25") (name "M_L_IN1") (class "Default")
      (node (ref "TB6612FNG") (pin "21") (pinfunction "AIN1_21") (pintype "bidirectional"))
      (node (ref "U$1") (pin "P$32") (pinfunction "CN2-4_P$32") (pintype "bidirectional"))
    )
    (net (code "26") (name "M_L_IN2") (class "Default")
      (node (ref "TB6612FNG") (pin "22") (pinfunction "AIN2_22") (pintype "bidirectional"))
      (node (ref "U$1") (pin "P$33") (pinfunction "CN2-5_P$33") (pintype "bidirectional"))
    )
    (net (code "27") (name "M_L_PWM") (class "Default")
      (node (ref "TB6612FNG") (pin "23") (pinfunction "PWMA_23") (pintype "bidirectional"))
      (node (ref "U$1") (pin "P$10") (pinfunction "CN1-10_P$10") (pintype "bidirectional"))
    )
    (net (code "28") (name "M_R_IN1") (class "Default")
      (node (ref "TB6612FNG") (pin "17") (pinfunction "BIN1_17") (pintype "bidirectional"))
      (node (ref "U$1") (pin "P$29") (pinfunction "CN2-1_P$29") (pintype "bidirectional"))
    )
    (net (code "29") (name "M_R_IN2") (class "Default")
      (node (ref "TB6612FNG") (pin "16") (pinfunction "BIN2_16") (pintype "bidirectional"))
      (node (ref "U$1") (pin "P$30") (pinfunction "CN2-2_P$30") (pintype "bidirectional"))
    )
    (net (code "30") (name "M_R_PWM") (class "Default")
      (node (ref "TB6612FNG") (pin "15") (pinfunction "PWMB_15") (pintype "bidirectional"))
      (node (ref "U$1") (pin "P$8") (pinfunction "CN1-8_P$8") (pintype "bidirectional"))
    )
    (net (code "31") (name "M_STBY") (class "Default")
      (node (ref "TB6612FNG") (pin "19") (pinfunction "STBY_19") (pintype "bidirectional"))
      (node (ref "U$1") (pin "P$34") (pinfunction "CN2-6_P$34") (pintype "bidirectional"))
    )
    (net (code "32") (name "Net-(7SEGL1-A)") (class "Default")
      (node (ref "7SEGL1") (pin "P$1") (pinfunction "A_P$1") (pintype "passive"))
      (node (ref "7S_R1") (pin "1") (pinfunction "1_1") (pintype "passive"))
    )
    (net (code "33") (name "Net-(7SEGL2-A)") (class "Default")
      (node (ref "7SEGL2") (pin "P$1") (pinfunction "A_P$1") (pintype "passive"))
      (node (ref "7S_R2") (pin "1") (pinfunction "1_1") (pintype "passive"))
    )
    (net (code "34") (name "Net-(7SEGL3-A)") (class "Default")
      (node (ref "7SEGL3") (pin "P$1") (pinfunction "A_P$1") (pintype "passive"))
      (node (ref "7S_R3") (pin "1") (pinfunction "1_1") (pintype "passive"))
    )
    (net (code "35") (name "Net-(7SEGL4-A)") (class "Default")
      (node (ref "7SEGL4") (pin "P$1") (pinfunction "A_P$1") (pintype "passive"))
      (node (ref "7S_R4") (pin "1") (pinfunction "1_1") (pintype "passive"))
    )
    (net (code "36") (name "Net-(7SEGL5-A)") (class "Default")
      (node (ref "7SEGL5") (pin "P$1") (pinfunction "A_P$1") (pintype "passive"))
      (node (ref "7S_R5") (pin "1") (pinfunction "1_1") (pintype "passive"))
    )
    (net (code "37") (name "Net-(7SEGL6-A)") (class "Default")
      (node (ref "7SEGL6") (pin "P$1") (pinfunction "A_P$1") (pintype "passive"))
      (node (ref "7S_R6") (pin "1") (pinfunction "1_1") (pintype "passive"))
    )
    (net (code "38") (name "Net-(7SEGL7-A)") (class "Default")
      (node (ref "7SEGL7") (pin "P$1") (pinfunction "A_P$1") (pintype "passive"))
      (node (ref "7S_R7") (pin "1") (pinfunction "1_1") (pintype "passive"))
    )
    (net (code "39") (name "Net-(CN_L_MOTOR-M+)") (class "Default")
      (node (ref "CN_L_MOTOR") (pin "P$1") (pinfunction "M+_P$1") (pintype "bidirectional"))
      (node (ref "TB6612FNG") (pin "1") (pinfunction "AO1_1") (pintype "bidirectional"))
      (node (ref "TB6612FNG") (pin "2") (pinfunction "AO1_2") (pintype "bidirectional"))
    )
    (net (code "40") (name "Net-(CN_L_MOTOR-M-)") (class "Default")
      (node (ref "CN_L_MOTOR") (pin "P$4") (pinfunction "M-_P$4") (pintype "bidirectional"))
      (node (ref "TB6612FNG") (pin "5") (pinfunction "AO2_5") (pintype "bidirectional"))
      (node (ref "TB6612FNG") (pin "6") (pinfunction "AO2_6") (pintype "bidirectional"))
    )
    (net (code "41") (name "Net-(CN_R_MOTOR-M+)") (class "Default")
      (node (ref "CN_R_MOTOR") (pin "P$1") (pinfunction "M+_P$1") (pintype "bidirectional"))
      (node (ref "TB6612FNG") (pin "11") (pinfunction "BO1_11") (pintype "bidirectional"))
      (node (ref "TB6612FNG") (pin "12") (pinfunction "BO1_12") (pintype "bidirectional"))
    )
    (net (code "42") (name "Net-(CN_R_MOTOR-M-)") (class "Default")
      (node (ref "CN_R_MOTOR") (pin "P$4") (pinfunction "M-_P$4") (pintype "bidirectional"))
      (node (ref "TB6612FNG") (pin "7") (pinfunction "BO2_7") (pintype "bidirectional"))
      (node (ref "TB6612FNG") (pin "8") (pinfunction "BO2_8") (pintype "bidirectional"))
    )
    (net (code "43") (name "Net-(LS1-N)") (class "Default")
      (node (ref "LS1") (pin "2") (pinfunction "N_2") (pintype "passive"))
      (node (ref "U$9") (pin "3") (pinfunction "D_3") (pintype "passive"))
    )
    (net (code "44") (name "Net-(POW_LED-A)") (class "Default")
      (node (ref "POW_LED") (pin "P$1") (pinfunction "A_P$1") (pintype "passive"))
      (node (ref "R29") (pin "1") (pinfunction "1_1") (pintype "passive"))
    )
    (net (code "45") (name "Net-(SEN_LF-LED-)") (class "Default")
      (node (ref "R_LF") (pin "2") (pinfunction "2_2") (pintype "passive"))
      (node (ref "SEN_LF") (pin "P$2") (pinfunction "LED-_P$2") (pintype "bidirectional"))
    )
    (net (code "46") (name "Net-(SEN_LS-LED-)") (class "Default")
      (node (ref "R_LS") (pin "2") (pinfunction "2_2") (pintype "passive"))
      (node (ref "SEN_LS") (pin "P$2") (pinfunction "LED-_P$2") (pintype "bidirectional"))
    )
    (net (code "47") (name "Net-(SEN_RF-LED-)") (class "Default")
      (node (ref "R_RF") (pin "2") (pinfunction "2_2") (pintype "passive"))
      (node (ref "SEN_RF") (pin "P$2") (pinfunction "LED-_P$2") (pintype "bidirectional"))
    )
    (net (code "48") (name "Net-(SEN_RS-LED-)") (class "Default")
      (node (ref "R_RS") (pin "2") (pinfunction "2_2") (pintype "passive"))
      (node (ref "SEN_RS") (pin "P$2") (pinfunction "LED-_P$2") (pintype "bidirectional"))
    )
    (net (code "49") (name "Net-(U$3-ON)") (class "Default")
      (node (ref "R1") (pin "1") (pinfunction "1_1") (pintype "passive"))
      (node (ref "U$3") (pin "P$3") (pinfunction "ON_P$3") (pintype "passive"))
      (node (ref "U$4") (pin "1") (pinfunction "G_1") (pintype "passive"))
    )
    (net (code "50") (name "Net-(U$4-S)") (class "Default")
      (node (ref "BATTERY") (pin "P$1") (pinfunction "P$1_P$1") (pintype "bidirectional"))
      (node (ref "R1") (pin "2") (pinfunction "2_2") (pintype "passive"))
      (node (ref "U$4") (pin "2") (pinfunction "S_2") (pintype "passive"))
    )
    (net (code "51") (name "Net-(U$5-D)") (class "Default")
      (node (ref "R_RS") (pin "1") (pinfunction "1_1") (pintype "passive"))
      (node (ref "U$5") (pin "3") (pinfunction "D_3") (pintype "passive"))
    )
    (net (code "52") (name "Net-(U$6-D)") (class "Default")
      (node (ref "R_LS") (pin "1") (pinfunction "1_1") (pintype "passive"))
      (node (ref "U$6") (pin "3") (pinfunction "D_3") (pintype "passive"))
    )
    (net (code "53") (name "Net-(U$7-D)") (class "Default")
      (node (ref "R_RF") (pin "1") (pinfunction "1_1") (pintype "passive"))
      (node (ref "U$7") (pin "3") (pinfunction "D_3") (pintype "passive"))
    )
    (net (code "54") (name "Net-(U$8-D)") (class "Default")
      (node (ref "R_LF") (pin "1") (pinfunction "1_1") (pintype "passive"))
      (node (ref "U$8") (pin "3") (pinfunction "D_3") (pintype "passive"))
    )
    (net (code "55") (name "Net-(U$9-G)") (class "Default")
      (node (ref "R8") (pin "2") (pinfunction "2_2") (pintype "passive"))
      (node (ref "R9") (pin "1") (pinfunction "1_1") (pintype "passive"))
      (node (ref "U$9") (pin "1") (pinfunction "G_1") (pintype "passive"))
    )
    (net (code "56") (name "Net-(U$13-4)") (class "Default")
      (node (ref "U$13") (pin "P$4") (pinfunction "4_P$4") (pintype "bidirectional"))
      (node (ref "U$13") (pin "P$6") (pinfunction "6_P$6") (pintype "bidirectional"))
    )
    (net (code "57") (name "Net-(U$17-A)") (class "Default")
      (node (ref "R17") (pin "1") (pinfunction "1_1") (pintype "passive"))
      (node (ref "U$17") (pin "P$1") (pinfunction "A_P$1") (pintype "passive"))
    )
    (net (code "58") (name "Net-(U$18-A)") (class "Default")
      (node (ref "R18") (pin "1") (pinfunction "1_1") (pintype "passive"))
      (node (ref "U$18") (pin "P$1") (pinfunction "A_P$1") (pintype "passive"))
    )
    (net (code "59") (name "Net-(U$19-A)") (class "Default")
      (node (ref "R19") (pin "1") (pinfunction "1_1") (pintype "passive"))
      (node (ref "U$19") (pin "P$1") (pinfunction "A_P$1") (pintype "passive"))
    )
    (net (code "60") (name "Net-(U$20-A)") (class "Default")
      (node (ref "R20") (pin "1") (pinfunction "1_1") (pintype "passive"))
      (node (ref "U$20") (pin "P$1") (pinfunction "A_P$1") (pintype "passive"))
    )
    (net (code "61") (name "Net-(U$21-A)") (class "Default")
      (node (ref "R21") (pin "1") (pinfunction "1_1") (pintype "passive"))
      (node (ref "U$21") (pin "P$1") (pinfunction "A_P$1") (pintype "passive"))
    )
    (net (code "62") (name "Net-(U1-NCS)") (class "Default")
      (node (ref "NCS_R1") (pin "2") (pinfunction "2_2") (pintype "passive"))
      (node (ref "NCS_R2") (pin "1") (pinfunction "1_1") (pintype "passive"))
      (node (ref "U1") (pin "22") (pinfunction "NCS_22") (pintype "bidirectional"))
    )
    (net (code "63") (name "Net-(U1-REGOUT)") (class "Default")
      (node (ref "U$27") (pin "1") (pinfunction "1_1") (pintype "passive"))
      (node (ref "U1") (pin "10") (pinfunction "REGOUT_10") (pintype "bidirectional"))
    )
    (net (code "64") (name "Net-(U1-SCL{slash}SCLK)") (class "Default")
      (node (ref "CLK_R1") (pin "2") (pinfunction "2_2") (pintype "passive"))
      (node (ref "CLK_R2") (pin "1") (pinfunction "1_1") (pintype "passive"))
      (node (ref "U1") (pin "23") (pinfunction "SCL/SCLK_23") (pintype "bidirectional"))
    )
    (net (code "65") (name "Net-(U1-SDA{slash}SDI)") (class "Default")
      (node (ref "MOSI_R1") (pin "2") (pinfunction "2_2") (pintype "passive"))
      (node (ref "MOSI_R2") (pin "1") (pinfunction "1_1") (pintype "passive"))
      (node (ref "U1") (pin "24") (pinfunction "SDA/SDI_24") (pintype "bidirectional"))
    )
    (net (code "66") (name "RS232_RXD") (class "Default")
      (node (ref "U$1") (pin "P$24") (pinfunction "CN1-24_P$24") (pintype "bidirectional"))
      (node (ref "U$13") (pin "P$3") (pinfunction "3_P$3") (pintype "bidirectional"))
    )
    (net (code "67") (name "RS232_TXD") (class "Default")
      (node (ref "U$1") (pin "P$25") (pinfunction "CN1-25_P$25") (pintype "bidirectional"))
      (node (ref "U$13") (pin "P$2") (pinfunction "2_P$2") (pintype "bidirectional"))
    )
    (net (code "68") (name "RSPCKA") (class "Default")
      (node (ref "CLK_R1") (pin "1") (pinfunction "1_1") (pintype "passive"))
      (node (ref "U$1") (pin "P$38") (pinfunction "CN2-10_P$38") (pintype "bidirectional"))
    )
    (net (code "69") (name "R_ENC_A") (class "Default")
      (node (ref "CN_R_MOTOR") (pin "P$6") (pinfunction "CA_P$6") (pintype "bidirectional"))
      (node (ref "U$1") (pin "P$14") (pinfunction "CN1-14_P$14") (pintype "bidirectional"))
    )
    (net (code "70") (name "R_ENC_B") (class "Default")
      (node (ref "CN_R_MOTOR") (pin "P$8") (pinfunction "CB_P$8") (pintype "bidirectional"))
      (node (ref "U$1") (pin "P$15") (pinfunction "CN1-15_P$15") (pintype "bidirectional"))
    )
    (net (code "71") (name "SEN_BAT") (class "Default")
      (node (ref "BTSEN_R1") (pin "2") (pinfunction "2_2") (pintype "passive"))
      (node (ref "BTSEN_R2") (pin "1") (pinfunction "1_1") (pintype "passive"))
      (node (ref "U$1") (pin "P$5") (pinfunction "CN1-5_P$5") (pintype "bidirectional"))
    )
    (net (code "72") (name "SEN_LF") (class "Default")
      (node (ref "R_S4") (pin "2") (pinfunction "2_2") (pintype "passive"))
      (node (ref "SEN_LF") (pin "P$1") (pinfunction "DIODE-_P$1") (pintype "bidirectional"))
      (node (ref "U$1") (pin "P$1") (pinfunction "CN1-1_P$1") (pintype "bidirectional"))
    )
    (net (code "73") (name "SEN_LS") (class "Default")
      (node (ref "R_S1") (pin "2") (pinfunction "2_2") (pintype "passive"))
      (node (ref "SEN_LS") (pin "P$1") (pinfunction "DIODE-_P$1") (pintype "bidirectional"))
      (node (ref "U$1") (pin "P$2") (pinfunction "CN1-2_P$2") (pintype "bidirectional"))
    )
    (net (code "74") (name "SEN_RF") (class "Default")
      (node (ref "R_S3") (pin "2") (pinfunction "2_2") (pintype "passive"))
      (node (ref "SEN_RF") (pin "P$1") (pinfunction "DIODE-_P$1") (pintype "bidirectional"))
      (node (ref "U$1") (pin "P$4") (pinfunction "CN1-4_P$4") (pintype "bidirectional"))
    )
    (net (code "75") (name "SEN_RS") (class "Default")
      (node (ref "R_S2") (pin "2") (pinfunction "2_2") (pintype "passive"))
      (node (ref "SEN_RS") (pin "P$1") (pinfunction "DIODE-_P$1") (pintype "bidirectional"))
      (node (ref "U$1") (pin "P$3") (pinfunction "CN1-3_P$3") (pintype "bidirectional"))
    )
    (net (code "76") (name "SSLA0") (class "Default")
      (node (ref "NCS_R1") (pin "1") (pinfunction "1_1") (pintype "passive"))
      (node (ref "U$1") (pin "P$37") (pinfunction "CN2-9_P$37") (pintype "bidirectional"))
    )
    (net (code "77") (name "VCC") (class "Default")
      (node (ref "5VREG") (pin "1") (pinfunction "IN_1") (pintype "input"))
      (node (ref "BTSEN_R1") (pin "1") (pinfunction "1_1") (pintype "passive"))
      (node (ref "C1") (pin "1") (pinfunction "1_1") (pintype "passive"))
      (node (ref "C2") (pin "1") (pinfunction "1_1") (pintype "passive"))
      (node (ref "EC1") (pin "1") (pinfunction "+_1") (pintype "passive"))
      (node (ref "TB6612FNG") (pin "13") (pinfunction "VM2_13") (pintype "bidirectional"))
      (node (ref "TB6612FNG") (pin "14") (pinfunction "VM3_14") (pintype "bidirectional"))
      (node (ref "TB6612FNG") (pin "24") (pinfunction "VM1_24") (pintype "bidirectional"))
      (node (ref "U$10") (pin "1") (pinfunction "1_1") (pintype "passive"))
      (node (ref "U$11") (pin "1") (pinfunction "1_1") (pintype "passive"))
      (node (ref "U$2") (pin "1") (pinfunction "+_1") (pintype "passive"))
      (node (ref "U$4") (pin "3") (pinfunction "D_3") (pintype "passive"))
    )
    (net (code "78") (name "unconnected-(CN_L_MOTOR-CZ-PadP$10)") (class "Default")
      (node (ref "CN_L_MOTOR") (pin "P$10") (pinfunction "CZ_P$10") (pintype "bidirectional"))
    )
    (net (code "79") (name "unconnected-(CN_L_MOTOR-C~{A}-PadP$5)") (class "Default")
      (node (ref "CN_L_MOTOR") (pin "P$5") (pinfunction "C~{A}_P$5") (pintype "bidirectional"))
    )
    (net (code "80") (name "unconnected-(CN_L_MOTOR-C~{B}-PadP$7)") (class "Default")
      (node (ref "CN_L_MOTOR") (pin "P$7") (pinfunction "C~{B}_P$7") (pintype "bidirectional"))
    )
    (net (code "81") (name "unconnected-(CN_L_MOTOR-C~{Z}-PadP$9)") (class "Default")
      (node (ref "CN_L_MOTOR") (pin "P$9") (pinfunction "C~{Z}_P$9") (pintype "bidirectional"))
    )
    (net (code "82") (name "unconnected-(CN_R_MOTOR-CZ-PadP$10)") (class "Default")
      (node (ref "CN_R_MOTOR") (pin "P$10") (pinfunction "CZ_P$10") (pintype "bidirectional"))
    )
    (net (code "83") (name "unconnected-(CN_R_MOTOR-C~{A}-PadP$5)") (class "Default")
      (node (ref "CN_R_MOTOR") (pin "P$5") (pinfunction "C~{A}_P$5") (pintype "bidirectional"))
    )
    (net (code "84") (name "unconnected-(CN_R_MOTOR-C~{B}-PadP$7)") (class "Default")
      (node (ref "CN_R_MOTOR") (pin "P$7") (pinfunction "C~{B}_P$7") (pintype "bidirectional"))
    )
    (net (code "85") (name "unconnected-(CN_R_MOTOR-C~{Z}-PadP$9)") (class "Default")
      (node (ref "CN_R_MOTOR") (pin "P$9") (pinfunction "C~{Z}_P$9") (pintype "bidirectional"))
    )
    (net (code "86") (name "unconnected-(U$1-CN1-6-PadP$6)") (class "Default")
      (node (ref "U$1") (pin "P$6") (pinfunction "CN1-6_P$6") (pintype "bidirectional"))
    )
    (net (code "87") (name "unconnected-(U$1-CN1-7-PadP$7)") (class "Default")
      (node (ref "U$1") (pin "P$7") (pinfunction "CN1-7_P$7") (pintype "bidirectional"))
    )
    (net (code "88") (name "unconnected-(U$1-CN1-13-PadP$13)") (class "Default")
      (node (ref "U$1") (pin "P$13") (pinfunction "CN1-13_P$13") (pintype "bidirectional"))
    )
    (net (code "89") (name "unconnected-(U$1-CN1-18-PadP$18)") (class "Default")
      (node (ref "U$1") (pin "P$18") (pinfunction "CN1-18_P$18") (pintype "bidirectional"))
    )
    (net (code "90") (name "unconnected-(U$1-CN1-19-PadP$19)") (class "Default")
      (node (ref "U$1") (pin "P$19") (pinfunction "CN1-19_P$19") (pintype "bidirectional"))
    )
    (net (code "91") (name "unconnected-(U$1-CN1-23-PadP$23)") (class "Default")
      (node (ref "U$1") (pin "P$23") (pinfunction "CN1-23_P$23") (pintype "bidirectional"))
    )
    (net (code "92") (name "unconnected-(U$1-CN1-26-PadP$26)") (class "Default")
      (node (ref "U$1") (pin "P$26") (pinfunction "CN1-26_P$26") (pintype "bidirectional"))
    )
    (net (code "93") (name "unconnected-(U$1-CN2-7-PadP$35)") (class "Default")
      (node (ref "U$1") (pin "P$35") (pinfunction "CN2-7_P$35") (pintype "bidirectional"))
    )
    (net (code "94") (name "unconnected-(U$1-CN2-8-PadP$36)") (class "Default")
      (node (ref "U$1") (pin "P$36") (pinfunction "CN2-8_P$36") (pintype "bidirectional"))
    )
    (net (code "95") (name "unconnected-(U$1-CN2-23-PadP$51)") (class "Default")
      (node (ref "U$1") (pin "P$51") (pinfunction "CN2-23_P$51") (pintype "bidirectional"))
    )
    (net (code "96") (name "unconnected-(U$1-CN2-25-PadP$53)") (class "Default")
      (node (ref "U$1") (pin "P$53") (pinfunction "CN2-25_P$53") (pintype "bidirectional"))
    )
    (net (code "97") (name "unconnected-(U$1-CN2-28-PadP$56)") (class "Default")
      (node (ref "U$1") (pin "P$56") (pinfunction "CN2-28_P$56") (pintype "bidirectional"))
    )
    (net (code "98") (name "unconnected-(U$3-OFF-PadP$1)") (class "Default")
      (node (ref "U$3") (pin "P$1") (pinfunction "OFF_P$1") (pintype "passive"))
    )
    (net (code "99") (name "unconnected-(U$13-1-PadP$1)") (class "Default")
      (node (ref "U$13") (pin "P$1") (pinfunction "1_P$1") (pintype "bidirectional"))
    )
    (net (code "100") (name "unconnected-(U$13-7-PadP$7)") (class "Default")
      (node (ref "U$13") (pin "P$7") (pinfunction "7_P$7") (pintype "bidirectional"))
    )
    (net (code "101") (name "unconnected-(U$13-8-PadP$8)") (class "Default")
      (node (ref "U$13") (pin "P$8") (pinfunction "8_P$8") (pintype "bidirectional"))
    )
    (net (code "102") (name "unconnected-(U$13-9-PadP$9)") (class "Default")
      (node (ref "U$13") (pin "P$9") (pinfunction "9_P$9") (pintype "bidirectional"))
    )
    (net (code "103") (name "unconnected-(U1-AUX_CL-Pad7)") (class "Default")
      (node (ref "U1") (pin "7") (pinfunction "AUX_CL_7") (pintype "bidirectional"))
    )
    (net (code "104") (name "unconnected-(U1-AUX_DA-Pad21)") (class "Default")
      (node (ref "U1") (pin "21") (pinfunction "AUX_DA_21") (pintype "bidirectional"))
    )
    (net (code "105") (name "unconnected-(U1-INT1-Pad12)") (class "Default")
      (node (ref "U1") (pin "12") (pinfunction "INT1_12") (pintype "bidirectional"))
    )
    (net (code "106") (name "unconnected-(U1-INT2-Pad19)") (class "Default")
      (node (ref "U1") (pin "19") (pinfunction "INT2_19") (pintype "bidirectional"))
    )
    (net (code "107") (name "unconnected-(U1-NC1-Pad1)") (class "Default")
      (node (ref "U1") (pin "1") (pinfunction "NC1_1") (pintype "bidirectional"))
    )
    (net (code "108") (name "unconnected-(U1-NC2-Pad2)") (class "Default")
      (node (ref "U1") (pin "2") (pinfunction "NC2_2") (pintype "bidirectional"))
    )
    (net (code "109") (name "unconnected-(U1-NC3-Pad3)") (class "Default")
      (node (ref "U1") (pin "3") (pinfunction "NC3_3") (pintype "bidirectional"))
    )
    (net (code "110") (name "unconnected-(U1-NC4-Pad4)") (class "Default")
      (node (ref "U1") (pin "4") (pinfunction "NC4_4") (pintype "bidirectional"))
    )
    (net (code "111") (name "unconnected-(U1-NC5-Pad5)") (class "Default")
      (node (ref "U1") (pin "5") (pinfunction "NC5_5") (pintype "bidirectional"))
    )
    (net (code "112") (name "unconnected-(U1-NC6-Pad6)") (class "Default")
      (node (ref "U1") (pin "6") (pinfunction "NC6_6") (pintype "bidirectional"))
    )
    (net (code "113") (name "unconnected-(U1-NC14-Pad14)") (class "Default")
      (node (ref "U1") (pin "14") (pinfunction "NC14_14") (pintype "bidirectional"))
    )
    (net (code "114") (name "unconnected-(U1-NC15-Pad15)") (class "Default")
      (node (ref "U1") (pin "15") (pinfunction "NC15_15") (pintype "bidirectional"))
    )
    (net (code "115") (name "unconnected-(U1-NC16-Pad16)") (class "Default")
      (node (ref "U1") (pin "16") (pinfunction "NC16_16") (pintype "bidirectional"))
    )
    (net (code "116") (name "unconnected-(U1-NC17-Pad17)") (class "Default")
      (node (ref "U1") (pin "17") (pinfunction "NC17_17") (pintype "bidirectional"))
    )
    (net (code "117") (name "unconnected-(U1-PAD-PadP$2)") (class "Default")
      (node (ref "U1") (pin "P$2") (pinfunction "PAD_P$2") (pintype "bidirectional"))
    )
  )
)
